# strobe.net
KiCad netlist of a schematic drawn in EAGLE
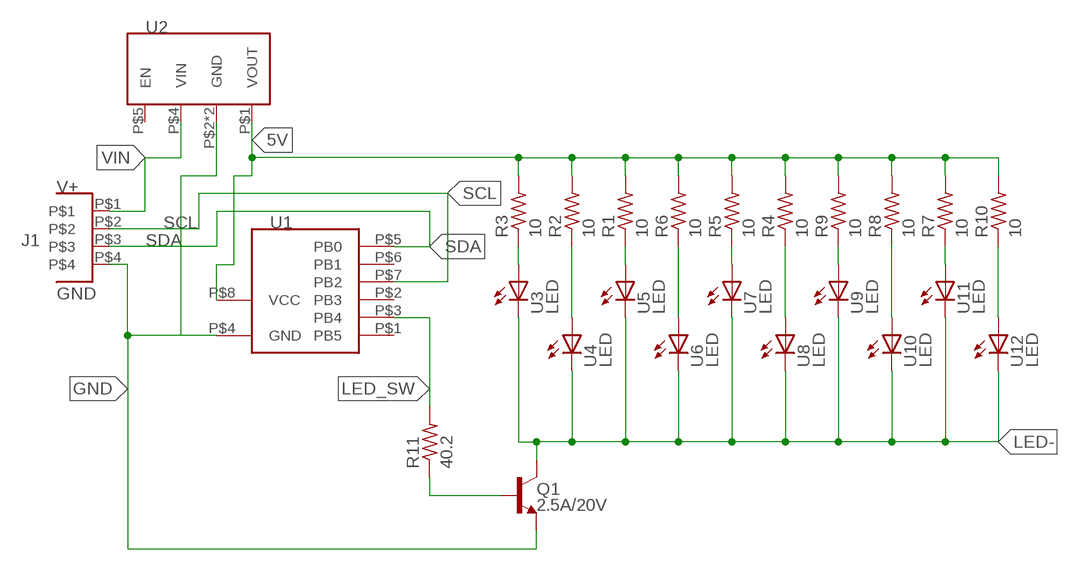
[diagram p0: schematic, sheet 1]

(export (version "E")
  (design (tool "Eeschema 10.0.6"))
  (components
    (comp (ref "J1")
      (value "MOLEX-04365004")
      (footprint "eagle-import:MOLEX-43650-04")
      (libsource (lib "eagle-import") (part "MOLEX-04365004"))
    )
    (comp (ref "Q1")
      (value "2.5A/20V")
      (footprint "eagle-import:SOT23-3")
      (libsource (lib "eagle-import") (part "TRANS_NPN-MMBT2222AL"))
    )
    (comp (ref "R1")
      (value "10")
      (footprint "eagle-import:R0805")
      (libsource (lib "eagle-import") (part "R-US_R0805"))
    )
    (comp (ref "R2")
      (value "10")
      (footprint "eagle-import:R0805")
      (libsource (lib "eagle-import") (part "R-US_R0805"))
    )
    (comp (ref "R3")
      (value "10")
      (footprint "eagle-import:R0805")
      (libsource (lib "eagle-import") (part "R-US_R0805"))
    )
    (comp (ref "R4")
      (value "10")
      (footprint "eagle-import:R0805")
      (libsource (lib "eagle-import") (part "R-US_R0805"))
    )
    (comp (ref "R5")
      (value "10")
      (footprint "eagle-import:R0805")
      (libsource (lib "eagle-import") (part "R-US_R0805"))
    )
    (comp (ref "R6")
      (value "10")
      (footprint "eagle-import:R0805")
      (libsource (lib "eagle-import") (part "R-US_R0805"))
    )
    (comp (ref "R7")
      (value "10")
      (footprint "eagle-import:R0805")
      (libsource (lib "eagle-import") (part "R-US_R0805"))
    )
    (comp (ref "R8")
      (value "10")
      (footprint "eagle-import:R0805")
      (libsource (lib "eagle-import") (part "R-US_R0805"))
    )
    (comp (ref "R9")
      (value "10")
      (footprint "eagle-import:R0805")
      (libsource (lib "eagle-import") (part "R-US_R0805"))
    )
    (comp (ref "R10")
      (value "10")
      (footprint "eagle-import:R0805")
      (libsource (lib "eagle-import") (part "R-US_R0805"))
    )
    (comp (ref "R11")
      (value "40.2")
      (footprint "eagle-import:R0805")
      (libsource (lib "eagle-import") (part "R-US_R0805"))
    )
    (comp (ref "U1")
      (value "ATTINY85")
      (footprint "eagle-import:8P3")
      (libsource (lib "eagle-import") (part "ATTINY85"))
    )
    (comp (ref "U2")
      (value "D24V25F5")
      (footprint "eagle-import:D24V25F5")
      (libsource (lib "eagle-import") (part "D24V25F5"))
    )
    (comp (ref "U3")
      (value "LED")
      (footprint "eagle-import:3030")
      (libsource (lib "eagle-import") (part "LED"))
    )
    (comp (ref "U4")
      (value "LED")
      (footprint "eagle-import:3030")
      (libsource (lib "eagle-import") (part "LED"))
    )
    (comp (ref "U5")
      (value "LED")
      (footprint "eagle-import:3030")
      (libsource (lib "eagle-import") (part "LED"))
    )
    (comp (ref "U6")
      (value "LED")
      (footprint "eagle-import:3030")
      (libsource (lib "eagle-import") (part "LED"))
    )
    (comp (ref "U7")
      (value "LED")
      (footprint "eagle-import:3030")
      (libsource (lib "eagle-import") (part "LED"))
    )
    (comp (ref "U8")
      (value "LED")
      (footprint "eagle-import:3030")
      (libsource (lib "eagle-import") (part "LED"))
    )
    (comp (ref "U9")
      (value "LED")
      (footprint "eagle-import:3030")
      (libsource (lib "eagle-import") (part "LED"))
    )
    (comp (ref "U10")
      (value "LED")
      (footprint "eagle-import:3030")
      (libsource (lib "eagle-import") (part "LED"))
    )
    (comp (ref "U11")
      (value "LED")
      (footprint "eagle-import:3030")
      (libsource (lib "eagle-import") (part "LED"))
    )
    (comp (ref "U12")
      (value "LED")
      (footprint "eagle-import:3030")
      (libsource (lib "eagle-import") (part "LED"))
    )
  )
  (nets
    (net (code "1") (name "5V") (class "Default")
      (node (ref "R1") (pin "2") (pinfunction "2_2") (pintype "passive"))
      (node (ref "R10") (pin "2") (pinfunction "2_2") (pintype "passive"))
      (node (ref "R2") (pin "2") (pinfunction "2_2") (pintype "passive"))
      (node (ref "R3") (pin "2") (pinfunction "2_2") (pintype "passive"))
      (node (ref "R4") (pin "2") (pinfunction "2_2") (pintype "passive"))
      (node (ref "R5") (pin "2") (pinfunction "2_2") (pintype "passive"))
      (node (ref "R6") (pin "2") (pinfunction "2_2") (pintype "passive"))
      (node (ref "R7") (pin "2") (pinfunction "2_2") (pintype "passive"))
      (node (ref "R8") (pin "2") (pinfunction "2_2") (pintype "passive"))
      (node (ref "R9") (pin "2") (pinfunction "2_2") (pintype "passive"))
      (node (ref "U1") (pin "P$8") (pinfunction "VCC_P$8") (pintype "bidirectional"))
      (node (ref "U2") (pin "P$1") (pinfunction "VOUT_P$1") (pintype "bidirectional"))
    )
    (net (code "2") (name "GND") (class "Default")
      (node (ref "J1") (pin "P$4") (pinfunction "P$4_P$4") (pintype "bidirectional"))
      (node (ref "Q1") (pin "2") (pinfunction "E_2") (pintype "passive"))
      (node (ref "U1") (pin "P$4") (pinfunction "GND_P$4") (pintype "bidirectional"))
      (node (ref "U2") (pin "P$2") (pinfunction "GND_P$2") (pintype "bidirectional"))
      (node (ref "U2") (pin "P$3") (pinfunction "GND_P$3") (pintype "bidirectional"))
    )
    (net (code "3") (name "LED-") (class "Default")
      (node (ref "Q1") (pin "3") (pinfunction "C_3") (pintype "passive"))
      (node (ref "U10") (pin "CATH") (pinfunction "C_CATH") (pintype "passive"))
      (node (ref "U11") (pin "CATH") (pinfunction "C_CATH") (pintype "passive"))
      (node (ref "U12") (pin "CATH") (pinfunction "C_CATH") (pintype "passive"))
      (node (ref "U3") (pin "CATH") (pinfunction "C_CATH") (pintype "passive"))
      (node (ref "U4") (pin "CATH") (pinfunction "C_CATH") (pintype "passive"))
      (node (ref "U5") (pin "CATH") (pinfunction "C_CATH") (pintype "passive"))
      (node (ref "U6") (pin "CATH") (pinfunction "C_CATH") (pintype "passive"))
      (node (ref "U7") (pin "CATH") (pinfunction "C_CATH") (pintype "passive"))
      (node (ref "U8") (pin "CATH") (pinfunction "C_CATH") (pintype "passive"))
      (node (ref "U9") (pin "CATH") (pinfunction "C_CATH") (pintype "passive"))
    )
    (net (code "4") (name "LED_SW") (class "Default")
      (node (ref "R11") (pin "2") (pinfunction "2_2") (pintype "passive"))
      (node (ref "U1") (pin "P$3") (pinfunction "PB4_P$3") (pintype "bidirectional"))
    )
    (net (code "5") (name "Net-(Q1-B)") (class "Default")
      (node (ref "Q1") (pin "1") (pinfunction "B_1") (pintype "passive"))
      (node (ref "R11") (pin "1") (pinfunction "1_1") (pintype "passive"))
    )
    (net (code "6") (name "Net-(U3-A)") (class "Default")
      (node (ref "R3") (pin "1") (pinfunction "1_1") (pintype "passive"))
      (node (ref "U3") (pin "ANODE") (pinfunction "A_ANODE") (pintype "passive"))
    )
    (net (code "7") (name "Net-(U4-A)") (class "Default")
      (node (ref "R2") (pin "1") (pinfunction "1_1") (pintype "passive"))
      (node (ref "U4") (pin "ANODE") (pinfunction "A_ANODE") (pintype "passive"))
    )
    (net (code "8") (name "Net-(U5-A)") (class "Default")
      (node (ref "R1") (pin "1") (pinfunction "1_1") (pintype "passive"))
      (node (ref "U5") (pin "ANODE") (pinfunction "A_ANODE") (pintype "passive"))
    )
    (net (code "9") (name "Net-(U6-A)") (class "Default")
      (node (ref "R6") (pin "1") (pinfunction "1_1") (pintype "passive"))
      (node (ref "U6") (pin "ANODE") (pinfunction "A_ANODE") (pintype "passive"))
    )
    (net (code "10") (name "Net-(U7-A)") (class "Default")
      (node (ref "R5") (pin "1") (pinfunction "1_1") (pintype "passive"))
      (node (ref "U7") (pin "ANODE") (pinfunction "A_ANODE") (pintype "passive"))
    )
    (net (code "11") (name "Net-(U8-A)") (class "Default")
      (node (ref "R4") (pin "1") (pinfunction "1_1") (pintype "passive"))
      (node (ref "U8") (pin "ANODE") (pinfunction "A_ANODE") (pintype "passive"))
    )
    (net (code "12") (name "Net-(U9-A)") (class "Default")
      (node (ref "R9") (pin "1") (pinfunction "1_1") (pintype "passive"))
      (node (ref "U9") (pin "ANODE") (pinfunction "A_ANODE") (pintype "passive"))
    )
    (net (code "13") (name "Net-(U10-A)") (class "Default")
      (node (ref "R8") (pin "1") (pinfunction "1_1") (pintype "passive"))
      (node (ref "U10") (pin "ANODE") (pinfunction "A_ANODE") (pintype "passive"))
    )
    (net (code "14") (name "Net-(U11-A)") (class "Default")
      (node (ref "R7") (pin "1") (pinfunction "1_1") (pintype "passive"))
      (node (ref "U11") (pin "ANODE") (pinfunction "A_ANODE") (pintype "passive"))
    )
    (net (code "15") (name "Net-(U12-A)") (class "Default")
      (node (ref "R10") (pin "1") (pinfunction "1_1") (pintype "passive"))
      (node (ref "U12") (pin "ANODE") (pinfunction "A_ANODE") (pintype "passive"))
    )
    (net (code "16") (name "SCL") (class "Default")
      (node (ref "J1") (pin "P$2") (pinfunction "P$2_P$2") (pintype "bidirectional"))
      (node (ref "U1") (pin "P$7") (pinfunction "PB2_P$7") (pintype "bidirectional"))
    )
    (net (code "17") (name "SDA") (class "Default")
      (node (ref "J1") (pin "P$3") (pinfunction "P$3_P$3") (pintype "bidirectional"))
      (node (ref "U1") (pin "P$5") (pinfunction "PB0_P$5") (pintype "bidirectional"))
    )
    (net (code "18") (name "VIN") (class "Default")
      (node (ref "J1") (pin "P$1") (pinfunction "P$1_P$1") (pintype "bidirectional"))
      (node (ref "U2") (pin "P$4") (pinfunction "VIN_P$4") (pintype "bidirectional"))
    )
    (net (code "19") (name "unconnected-(U1-PB1-PadP$6)") (class "Default")
      (node (ref "U1") (pin "P$6") (pinfunction "PB1_P$6") (pintype "bidirectional"))
    )
    (net (code "20") (name "unconnected-(U1-PB3-PadP$2)") (class "Default")
      (node (ref "U1") (pin "P$2") (pinfunction "PB3_P$2") (pintype "bidirectional"))
    )
    (net (code "21") (name "unconnected-(U1-PB5-PadP$1)") (class "Default")
      (node (ref "U1") (pin "P$1") (pinfunction "PB5_P$1") (pintype "bidirectional"))
    )
    (net (code "22") (name "unconnected-(U2-EN-PadP$5)") (class "Default")
      (node (ref "U2") (pin "P$5") (pinfunction "EN_P$5") (pintype "bidirectional"))
    )
  )
)
